# Thermostat_V1_0.net
KiCad netlist of a schematic drawn in EAGLE
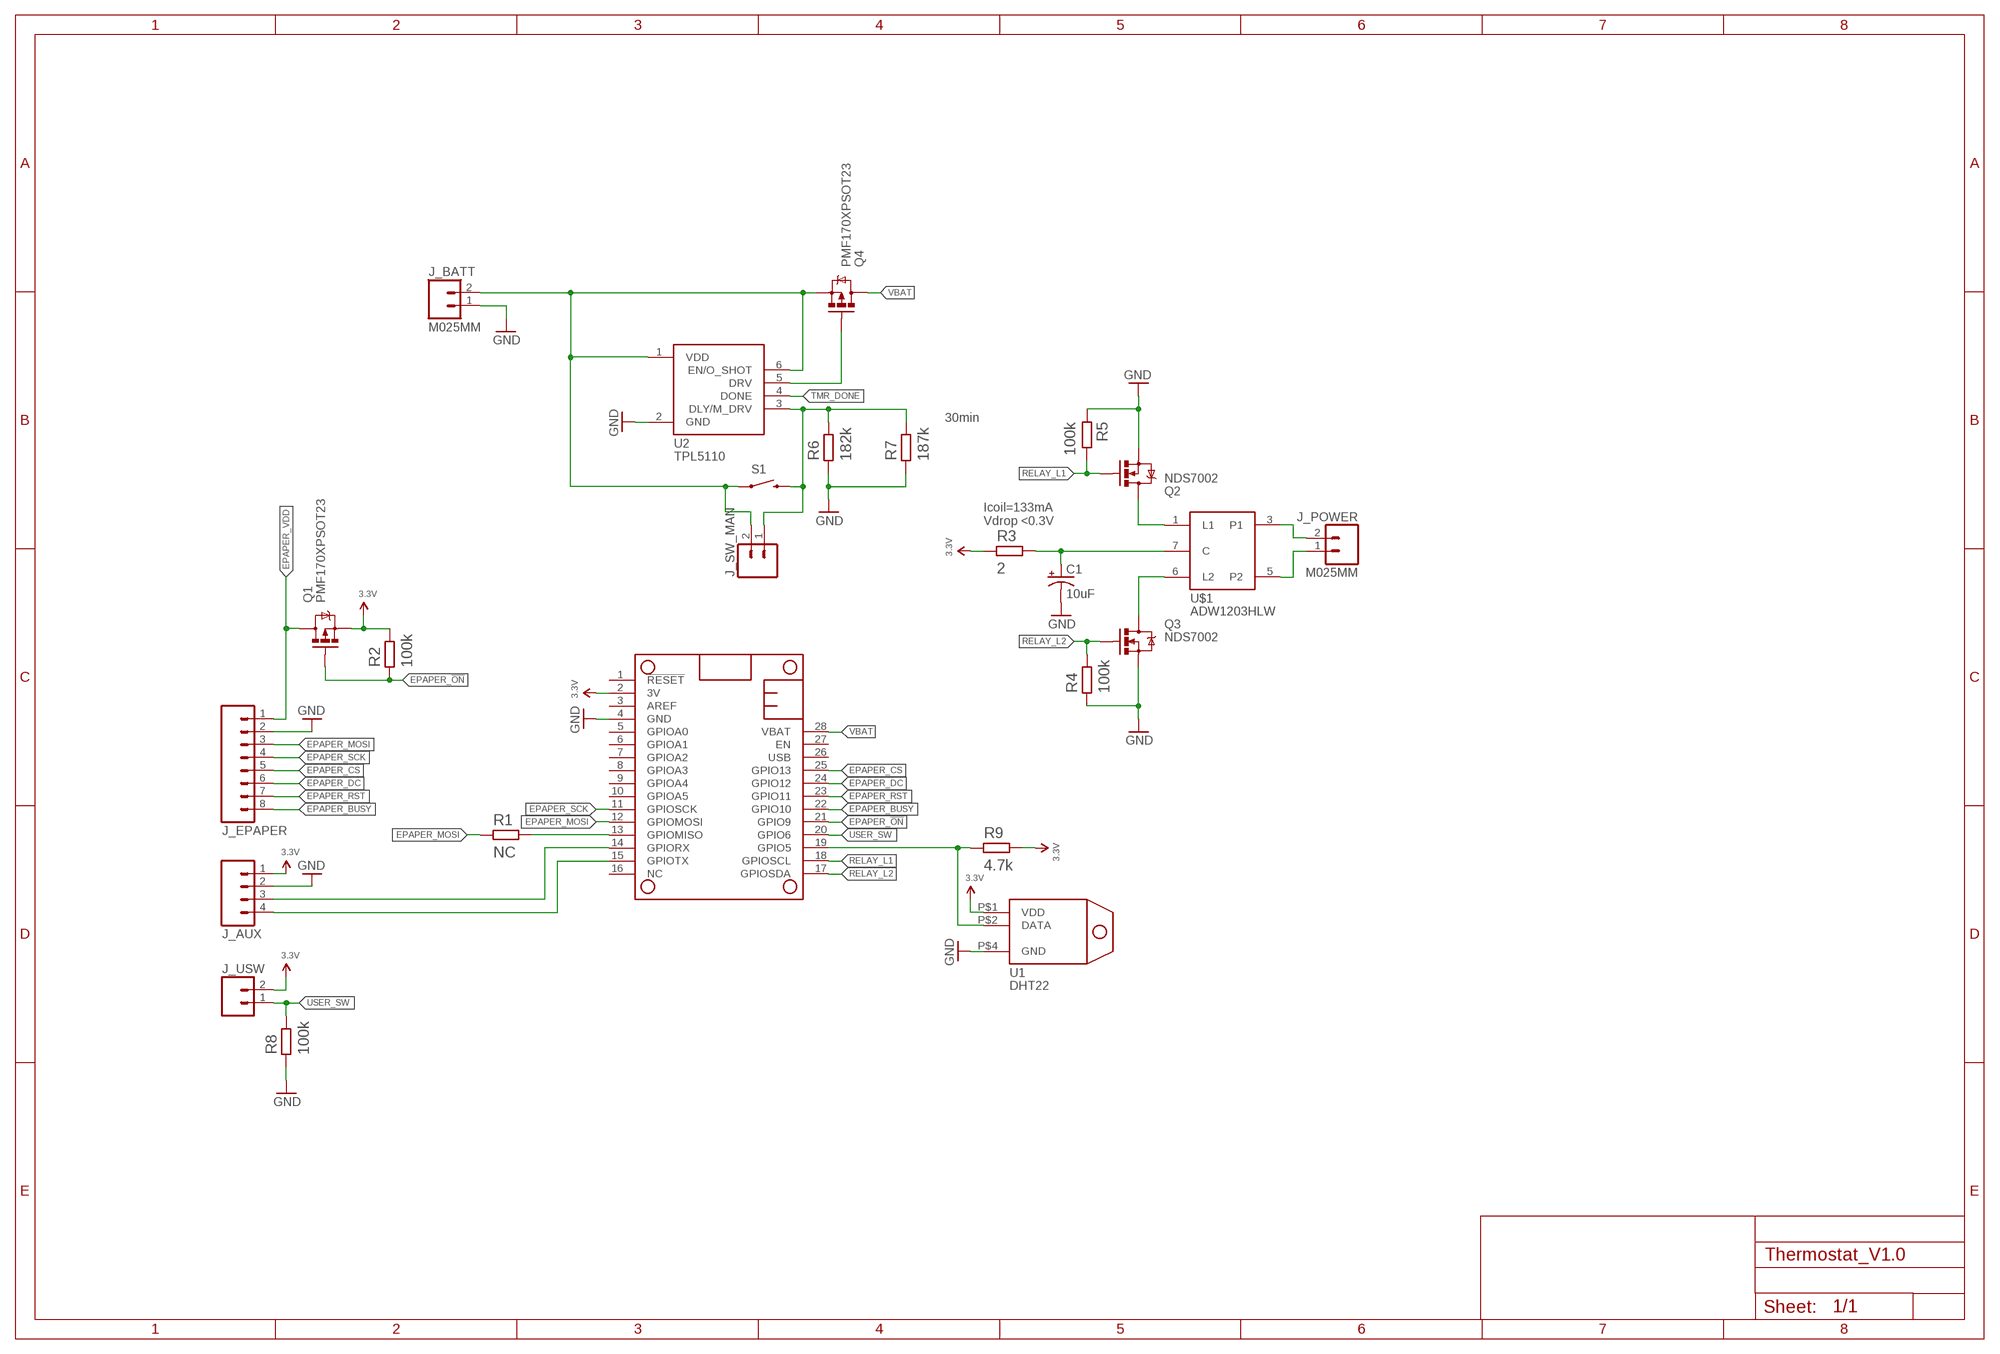
[diagram p0: schematic, sheet 1]

(export (version "E")
  (design (tool "Eeschema 10.0.6"))
  (components
    (comp (ref "C1")
      (value "10uF")
      (footprint "eagle-import:CPOL-RADIAL-100UF-25V")
      (libsource (lib "eagle-import") (part "CAP_POLPTH1"))
    )
    (comp (ref "J_AUX")
      (value "M04LOCK")
      (footprint "eagle-import:1X04_LOCK")
      (libsource (lib "eagle-import") (part "M04LOCK"))
    )
    (comp (ref "J_BATT")
      (value "M025MM")
      (footprint "eagle-import:SCREWTERMINAL-5MM-2")
      (libsource (lib "eagle-import") (part "M025MM"))
    )
    (comp (ref "J_EPAPER")
      (value "M081X08")
      (footprint "eagle-import:1X08")
      (libsource (lib "eagle-import") (part "M081X08"))
    )
    (comp (ref "J_POWER")
      (value "M025MM")
      (footprint "eagle-import:SCREWTERMINAL-5MM-2")
      (libsource (lib "eagle-import") (part "M025MM"))
    )
    (comp (ref "J_SW_MAN")
      (value "M023.5MM-NO_SILK")
      (footprint "eagle-import:SCREWTERMINAL-3.5MM-2-NS")
      (libsource (lib "eagle-import") (part "M023.5MM-NO_SILK"))
    )
    (comp (ref "J_USW")
      (value "M023.5MM-NO_SILK")
      (footprint "eagle-import:SCREWTERMINAL-3.5MM-2-NS")
      (libsource (lib "eagle-import") (part "M023.5MM-NO_SILK"))
    )
    (comp (ref "MS1")
      (value "FEATHERWING")
      (footprint "eagle-import:FEATHERWING")
      (libsource (lib "eagle-import") (part "FEATHERWING"))
    )
    (comp (ref "Q1")
      (value "PMF170XPSOT23")
      (footprint "eagle-import:SOT23")
      (libsource (lib "eagle-import") (part "PMF170XPSOT23"))
    )
    (comp (ref "Q2")
      (value "NDS7002")
      (footprint "eagle-import:SOT23")
      (libsource (lib "eagle-import") (part "NDS7002"))
    )
    (comp (ref "Q3")
      (value "NDS7002")
      (footprint "eagle-import:SOT23")
      (libsource (lib "eagle-import") (part "NDS7002"))
    )
    (comp (ref "Q4")
      (value "PMF170XPSOT23")
      (footprint "eagle-import:SOT23")
      (libsource (lib "eagle-import") (part "PMF170XPSOT23"))
    )
    (comp (ref "R1")
      (value "NC")
      (footprint "eagle-import:R0805")
      (libsource (lib "eagle-import") (part "R0805"))
    )
    (comp (ref "R2")
      (value "100k")
      (footprint "eagle-import:R0805")
      (libsource (lib "eagle-import") (part "R0805"))
    )
    (comp (ref "R3")
      (value "2")
      (footprint "eagle-import:R0805")
      (libsource (lib "eagle-import") (part "R0805"))
    )
    (comp (ref "R4")
      (value "100k")
      (footprint "eagle-import:R0805")
      (libsource (lib "eagle-import") (part "R0805"))
    )
    (comp (ref "R5")
      (value "100k")
      (footprint "eagle-import:R0805")
      (libsource (lib "eagle-import") (part "R0805"))
    )
    (comp (ref "R6")
      (value "182k")
      (footprint "eagle-import:1210")
      (libsource (lib "eagle-import") (part "R1210"))
    )
    (comp (ref "R7")
      (value "187k")
      (footprint "eagle-import:1210")
      (libsource (lib "eagle-import") (part "R1210"))
    )
    (comp (ref "R8")
      (value "100k")
      (footprint "eagle-import:R0805")
      (libsource (lib "eagle-import") (part "R0805"))
    )
    (comp (ref "R9")
      (value "4.7k")
      (footprint "eagle-import:R0805")
      (libsource (lib "eagle-import") (part "R0805"))
    )
    (comp (ref "S1")
      (value "SWITCH-MOMENTARY-2SMD-4")
      (footprint "eagle-import:TACTILE_SWITCH_TALL")
      (libsource (lib "eagle-import") (part "SWITCH-MOMENTARY-2SMD-4"))
    )
    (comp (ref "U$1")
      (value "ADW1203HLW")
      (footprint "eagle-import:DW_RELAY")
      (libsource (lib "eagle-import") (part "ADW1203HLW"))
    )
    (comp (ref "U1")
      (value "DHT22")
      (footprint "eagle-import:DHT22")
      (libsource (lib "eagle-import") (part "DHT22"))
    )
    (comp (ref "U2")
      (value "TPL5110")
      (footprint "eagle-import:SOT23-6")
      (libsource (lib "eagle-import") (part "TPL5110"))
    )
  )
  (nets
    (net (code "1") (name "/EPAPER_~{ON}") (class "Default")
      (node (ref "MS1") (pin "21") (pinfunction "GPIO9_21") (pintype "bidirectional"))
      (node (ref "Q1") (pin "1") (pinfunction "G_1") (pintype "passive"))
      (node (ref "R2") (pin "1") (pinfunction "1_1") (pintype "bidirectional"))
    )
    (net (code "2") (name "/USB") (class "Default")
      (node (ref "MS1") (pin "26") (pinfunction "USB_26") (pintype "power_in"))
    )
    (net (code "3") (name "3.3V") (class "Default")
      (node (ref "J_AUX") (pin "1") (pinfunction "1_1") (pintype "passive"))
      (node (ref "J_USW") (pin "2") (pinfunction "2_2") (pintype "passive"))
      (node (ref "MS1") (pin "2") (pinfunction "3V_2") (pintype "power_in"))
      (node (ref "Q1") (pin "2") (pinfunction "S_2") (pintype "passive"))
      (node (ref "R2") (pin "2") (pinfunction "2_2") (pintype "bidirectional"))
      (node (ref "R3") (pin "1") (pinfunction "1_1") (pintype "bidirectional"))
      (node (ref "R9") (pin "2") (pinfunction "2_2") (pintype "bidirectional"))
      (node (ref "U1") (pin "P$1") (pinfunction "VDD_P$1") (pintype "bidirectional"))
    )
    (net (code "4") (name "EPAPER_BUSY") (class "Default")
      (node (ref "J_EPAPER") (pin "8") (pinfunction "8_8") (pintype "passive"))
      (node (ref "MS1") (pin "22") (pinfunction "GPIO10_22") (pintype "bidirectional"))
    )
    (net (code "5") (name "EPAPER_CS") (class "Default")
      (node (ref "J_EPAPER") (pin "5") (pinfunction "5_5") (pintype "passive"))
      (node (ref "MS1") (pin "25") (pinfunction "GPIO13_25") (pintype "bidirectional"))
    )
    (net (code "6") (name "EPAPER_DC") (class "Default")
      (node (ref "J_EPAPER") (pin "6") (pinfunction "6_6") (pintype "passive"))
      (node (ref "MS1") (pin "24") (pinfunction "GPIO12_24") (pintype "bidirectional"))
    )
    (net (code "7") (name "EPAPER_MOSI") (class "Default")
      (node (ref "J_EPAPER") (pin "3") (pinfunction "3_3") (pintype "passive"))
      (node (ref "MS1") (pin "12") (pinfunction "GPIOMOSI_12") (pintype "bidirectional"))
      (node (ref "R1") (pin "1") (pinfunction "1_1") (pintype "bidirectional"))
    )
    (net (code "8") (name "EPAPER_RST") (class "Default")
      (node (ref "J_EPAPER") (pin "7") (pinfunction "7_7") (pintype "passive"))
      (node (ref "MS1") (pin "23") (pinfunction "GPIO11_23") (pintype "bidirectional"))
    )
    (net (code "9") (name "EPAPER_SCK") (class "Default")
      (node (ref "J_EPAPER") (pin "4") (pinfunction "4_4") (pintype "passive"))
      (node (ref "MS1") (pin "11") (pinfunction "GPIOSCK_11") (pintype "bidirectional"))
    )
    (net (code "10") (name "EPAPER_VDD") (class "Default")
      (node (ref "J_EPAPER") (pin "1") (pinfunction "1_1") (pintype "passive"))
      (node (ref "Q1") (pin "3") (pinfunction "D_3") (pintype "passive"))
    )
    (net (code "11") (name "GND") (class "Default")
      (node (ref "C1") (pin "2") (pinfunction "-_2") (pintype "passive"))
      (node (ref "J_AUX") (pin "2") (pinfunction "2_2") (pintype "passive"))
      (node (ref "J_BATT") (pin "1") (pinfunction "1_1") (pintype "passive"))
      (node (ref "J_EPAPER") (pin "2") (pinfunction "2_2") (pintype "passive"))
      (node (ref "MS1") (pin "4") (pinfunction "GND_4") (pintype "power_in"))
      (node (ref "Q2") (pin "2") (pinfunction "S_2") (pintype "passive"))
      (node (ref "Q3") (pin "2") (pinfunction "S_2") (pintype "passive"))
      (node (ref "R4") (pin "1") (pinfunction "1_1") (pintype "bidirectional"))
      (node (ref "R5") (pin "1") (pinfunction "1_1") (pintype "bidirectional"))
      (node (ref "R6") (pin "1") (pinfunction "1_1") (pintype "bidirectional"))
      (node (ref "R7") (pin "1") (pinfunction "1_1") (pintype "bidirectional"))
      (node (ref "R8") (pin "1") (pinfunction "1_1") (pintype "bidirectional"))
      (node (ref "U1") (pin "P$4") (pinfunction "GND_P$4") (pintype "bidirectional"))
      (node (ref "U2") (pin "2") (pinfunction "GND_2") (pintype "bidirectional"))
    )
    (net (code "12") (name "Net-(C1-+)") (class "Default")
      (node (ref "C1") (pin "1") (pinfunction "+_1") (pintype "passive"))
      (node (ref "R3") (pin "2") (pinfunction "2_2") (pintype "bidirectional"))
      (node (ref "U$1") (pin "7") (pinfunction "C_7") (pintype "bidirectional"))
    )
    (net (code "13") (name "Net-(MS1-GPIO5)") (class "Default")
      (node (ref "MS1") (pin "19") (pinfunction "GPIO5_19") (pintype "bidirectional"))
      (node (ref "R9") (pin "1") (pinfunction "1_1") (pintype "bidirectional"))
      (node (ref "U1") (pin "P$2") (pinfunction "DATA_P$2") (pintype "bidirectional"))
    )
    (net (code "14") (name "Net-(MS1-GPIOMISO)") (class "Default")
      (node (ref "MS1") (pin "13") (pinfunction "GPIOMISO_13") (pintype "bidirectional"))
      (node (ref "R1") (pin "2") (pinfunction "2_2") (pintype "bidirectional"))
    )
    (net (code "15") (name "Net-(MS1-GPIORX)") (class "Default")
      (node (ref "J_AUX") (pin "3") (pinfunction "3_3") (pintype "passive"))
      (node (ref "MS1") (pin "14") (pinfunction "GPIORX_14") (pintype "bidirectional"))
    )
    (net (code "16") (name "Net-(MS1-GPIOTX)") (class "Default")
      (node (ref "J_AUX") (pin "4") (pinfunction "4_4") (pintype "passive"))
      (node (ref "MS1") (pin "15") (pinfunction "GPIOTX_15") (pintype "bidirectional"))
    )
    (net (code "17") (name "Net-(Q2-D)") (class "Default")
      (node (ref "Q2") (pin "3") (pinfunction "D_3") (pintype "passive"))
      (node (ref "U$1") (pin "1") (pinfunction "L1_1") (pintype "bidirectional"))
    )
    (net (code "18") (name "Net-(Q3-D)") (class "Default")
      (node (ref "Q3") (pin "3") (pinfunction "D_3") (pintype "passive"))
      (node (ref "U$1") (pin "6") (pinfunction "L2_6") (pintype "bidirectional"))
    )
    (net (code "19") (name "Net-(Q4-G)") (class "Default")
      (node (ref "Q4") (pin "1") (pinfunction "G_1") (pintype "passive"))
      (node (ref "U2") (pin "5") (pinfunction "DRV_5") (pintype "bidirectional"))
    )
    (net (code "20") (name "Net-(Q4-S)") (class "Default")
      (node (ref "J_BATT") (pin "2") (pinfunction "2_2") (pintype "passive"))
      (node (ref "J_SW_MAN") (pin "2") (pinfunction "2_2") (pintype "passive"))
      (node (ref "Q4") (pin "2") (pinfunction "S_2") (pintype "passive"))
      (node (ref "S1") (pin "A2") (pinfunction "1_A2") (pintype "passive"))
      (node (ref "U2") (pin "1") (pinfunction "VDD_1") (pintype "bidirectional"))
      (node (ref "U2") (pin "6") (pinfunction "EN/O_SHOT_6") (pintype "bidirectional"))
    )
    (net (code "21") (name "Net-(S1-2)") (class "Default")
      (node (ref "J_SW_MAN") (pin "1") (pinfunction "1_1") (pintype "passive"))
      (node (ref "R6") (pin "2") (pinfunction "2_2") (pintype "bidirectional"))
      (node (ref "R7") (pin "2") (pinfunction "2_2") (pintype "bidirectional"))
      (node (ref "S1") (pin "B2") (pinfunction "2_B2") (pintype "passive"))
      (node (ref "U2") (pin "3") (pinfunction "DLY/M_DRV_3") (pintype "bidirectional"))
    )
    (net (code "22") (name "Net-(U$1-P1)") (class "Default")
      (node (ref "J_POWER") (pin "2") (pinfunction "2_2") (pintype "passive"))
      (node (ref "U$1") (pin "3") (pinfunction "P1_3") (pintype "bidirectional"))
    )
    (net (code "23") (name "Net-(U$1-P2)") (class "Default")
      (node (ref "J_POWER") (pin "1") (pinfunction "1_1") (pintype "passive"))
      (node (ref "U$1") (pin "5") (pinfunction "P2_5") (pintype "bidirectional"))
    )
    (net (code "24") (name "RELAY_L1") (class "Default")
      (node (ref "MS1") (pin "18") (pinfunction "GPIOSCL_18") (pintype "bidirectional"))
      (node (ref "Q2") (pin "1") (pinfunction "G_1") (pintype "passive"))
      (node (ref "R5") (pin "2") (pinfunction "2_2") (pintype "bidirectional"))
    )
    (net (code "25") (name "RELAY_L2") (class "Default")
      (node (ref "MS1") (pin "17") (pinfunction "GPIOSDA_17") (pintype "bidirectional"))
      (node (ref "Q3") (pin "1") (pinfunction "G_1") (pintype "passive"))
      (node (ref "R4") (pin "2") (pinfunction "2_2") (pintype "bidirectional"))
    )
    (net (code "26") (name "TMR_DONE") (class "Default")
      (node (ref "U2") (pin "4") (pinfunction "DONE_4") (pintype "bidirectional"))
    )
    (net (code "27") (name "USER_SW") (class "Default")
      (node (ref "J_USW") (pin "1") (pinfunction "1_1") (pintype "passive"))
      (node (ref "MS1") (pin "20") (pinfunction "GPIO6_20") (pintype "bidirectional"))
      (node (ref "R8") (pin "2") (pinfunction "2_2") (pintype "bidirectional"))
    )
    (net (code "28") (name "VBAT") (class "Default")
      (node (ref "MS1") (pin "28") (pinfunction "VBAT_28") (pintype "power_in"))
      (node (ref "Q4") (pin "3") (pinfunction "D_3") (pintype "passive"))
    )
    (net (code "29") (name "unconnected-(MS1-AREF-Pad3)") (class "Default")
      (node (ref "MS1") (pin "3") (pinfunction "AREF_3") (pintype "passive"))
    )
    (net (code "30") (name "unconnected-(MS1-EN-Pad27)") (class "Default")
      (node (ref "MS1") (pin "27") (pinfunction "EN_27") (pintype "passive"))
    )
    (net (code "31") (name "unconnected-(MS1-GPIOA0-Pad5)") (class "Default")
      (node (ref "MS1") (pin "5") (pinfunction "GPIOA0_5") (pintype "bidirectional"))
    )
    (net (code "32") (name "unconnected-(MS1-GPIOA1-Pad6)") (class "Default")
      (node (ref "MS1") (pin "6") (pinfunction "GPIOA1_6") (pintype "bidirectional"))
    )
    (net (code "33") (name "unconnected-(MS1-GPIOA2-Pad7)") (class "Default")
      (node (ref "MS1") (pin "7") (pinfunction "GPIOA2_7") (pintype "bidirectional"))
    )
    (net (code "34") (name "unconnected-(MS1-GPIOA3-Pad8)") (class "Default")
      (node (ref "MS1") (pin "8") (pinfunction "GPIOA3_8") (pintype "bidirectional"))
    )
    (net (code "35") (name "unconnected-(MS1-GPIOA4-Pad9)") (class "Default")
      (node (ref "MS1") (pin "9") (pinfunction "GPIOA4_9") (pintype "bidirectional"))
    )
    (net (code "36") (name "unconnected-(MS1-GPIOA5-Pad10)") (class "Default")
      (node (ref "MS1") (pin "10") (pinfunction "GPIOA5_10") (pintype "bidirectional"))
    )
    (net (code "37") (name "unconnected-(MS1-NC-Pad16)") (class "Default")
      (node (ref "MS1") (pin "16") (pinfunction "NC_16") (pintype "passive"))
    )
    (net (code "38") (name "unconnected-(MS1-~{RESET}-Pad1)") (class "Default")
      (node (ref "MS1") (pin "1") (pinfunction "~{RESET}_1") (pintype "input"))
    )
  )
)
